# RT_SUPER_EXT.net
KiCad netlist of a schematic drawn in Altium Designer
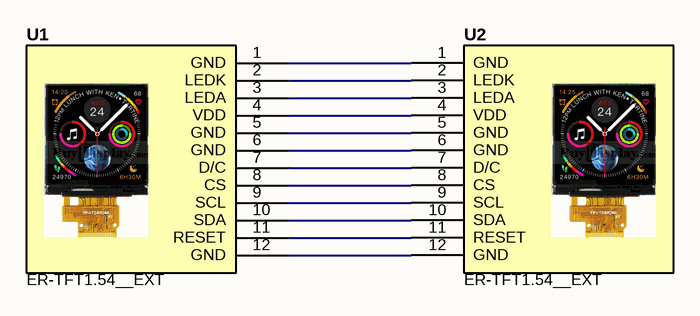
[diagram p0: RT_SUPER_EXT.SchDoc]

(export (version "E")
  (design (tool "Eeschema 10.0.6"))
  (components
    (comp (ref "U1")
      (value "ER-TFT1.54__EXT")
      (footprint "ER-TFT1.54-1 - EXT")
      (description "EXTENTION FOOTPRINT")
      (fields
        (field (name "MANUFACTURER") "Buy Display")
        (field (name "MANUFACTURER PART NUMBER") "ER-TFT1.54-1")
      )
      (libsource (lib "eDisplay") (part "ER-TFT1.54__EXT"))
    )
    (comp (ref "U2")
      (value "ER-TFT1.54__EXT")
      (footprint "ER-TFT1.54-1 - EXT")
      (description "EXTENTION FOOTPRINT")
      (fields
        (field (name "MANUFACTURER") "Buy Display")
        (field (name "MANUFACTURER PART NUMBER") "ER-TFT1.54-1")
      )
      (libsource (lib "") (part "ER-TFT1.54__EXT_1"))
    )
  )
  (nets
    (net (code "1") (name "Net-(U1-CS)") (class "Default")
      (node (ref "U1") (pin "8") (pinfunction "CS_8") (pintype "passive"))
      (node (ref "U2") (pin "8") (pinfunction "CS_8") (pintype "passive"))
    )
    (net (code "2") (name "Net-(U1-D{slash}C)") (class "Default")
      (node (ref "U1") (pin "7") (pinfunction "D/C_7") (pintype "passive"))
      (node (ref "U2") (pin "7") (pinfunction "D/C_7") (pintype "passive"))
    )
    (net (code "3") (name "Net-(U1-GND-Pad1)") (class "Default")
      (node (ref "U1") (pin "1") (pinfunction "GND_1") (pintype "passive"))
      (node (ref "U2") (pin "1") (pinfunction "GND_1") (pintype "passive"))
    )
    (net (code "4") (name "Net-(U1-GND-Pad5)") (class "Default")
      (node (ref "U1") (pin "5") (pinfunction "GND_5") (pintype "passive"))
      (node (ref "U2") (pin "5") (pinfunction "GND_5") (pintype "passive"))
    )
    (net (code "5") (name "Net-(U1-GND-Pad6)") (class "Default")
      (node (ref "U1") (pin "6") (pinfunction "GND_6") (pintype "passive"))
      (node (ref "U2") (pin "6") (pinfunction "GND_6") (pintype "passive"))
    )
    (net (code "6") (name "Net-(U1-GND-Pad12)") (class "Default")
      (node (ref "U1") (pin "12") (pinfunction "GND_12") (pintype "passive"))
      (node (ref "U2") (pin "12") (pinfunction "GND_12") (pintype "passive"))
    )
    (net (code "7") (name "Net-(U1-LEDA)") (class "Default")
      (node (ref "U1") (pin "3") (pinfunction "LEDA_3") (pintype "passive"))
      (node (ref "U2") (pin "3") (pinfunction "LEDA_3") (pintype "passive"))
    )
    (net (code "8") (name "Net-(U1-LEDK)") (class "Default")
      (node (ref "U1") (pin "2") (pinfunction "LEDK_2") (pintype "passive"))
      (node (ref "U2") (pin "2") (pinfunction "LEDK_2") (pintype "passive"))
    )
    (net (code "9") (name "Net-(U1-RESET)") (class "Default")
      (node (ref "U1") (pin "11") (pinfunction "RESET_11") (pintype "passive"))
      (node (ref "U2") (pin "11") (pinfunction "RESET_11") (pintype "passive"))
    )
    (net (code "10") (name "Net-(U1-SCL)") (class "Default")
      (node (ref "U1") (pin "9") (pinfunction "SCL_9") (pintype "passive"))
      (node (ref "U2") (pin "9") (pinfunction "SCL_9") (pintype "passive"))
    )
    (net (code "11") (name "Net-(U1-SDA)") (class "Default")
      (node (ref "U1") (pin "10") (pinfunction "SDA_10") (pintype "passive"))
      (node (ref "U2") (pin "10") (pinfunction "SDA_10") (pintype "passive"))
    )
    (net (code "12") (name "Net-(U1-VDD)") (class "Default")
      (node (ref "U1") (pin "4") (pinfunction "VDD_4") (pintype "passive"))
      (node (ref "U2") (pin "4") (pinfunction "VDD_4") (pintype "passive"))
    )
  )
)
